# Master_MicroController_LED_Driver.net
KiCad netlist of a schematic drawn in Altium Designer
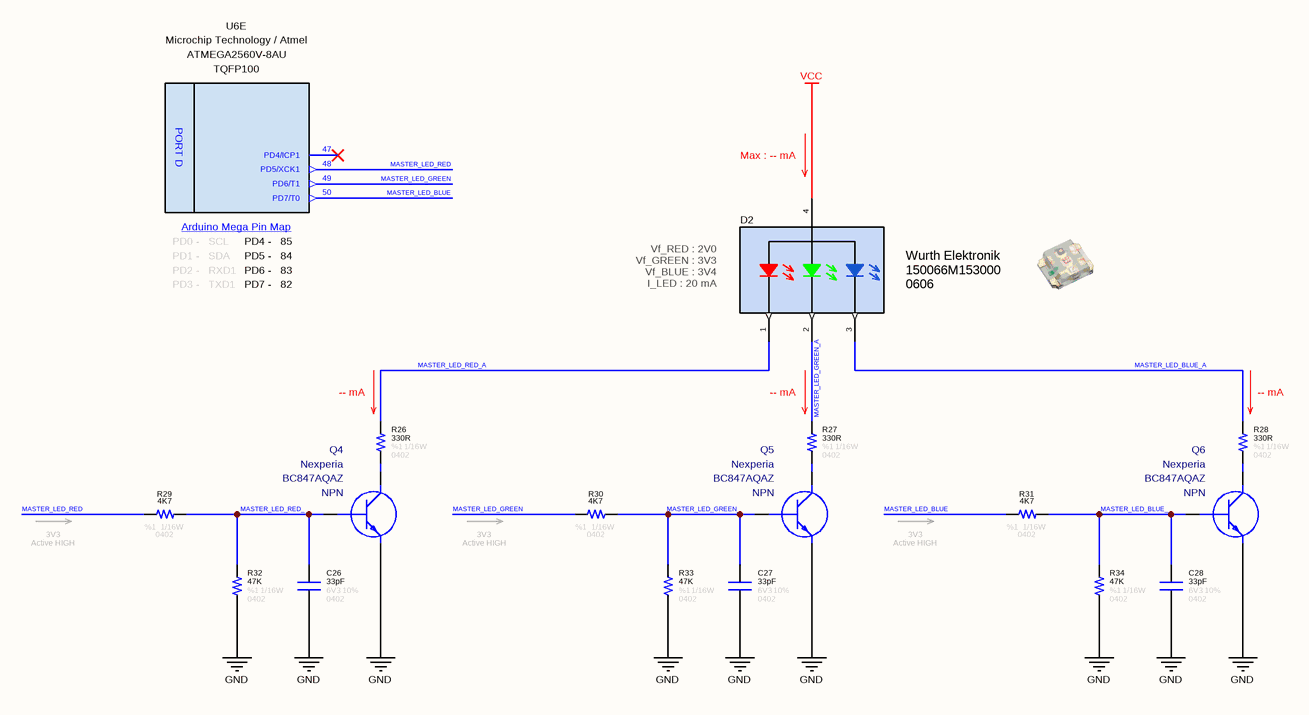
[diagram p0: Master MicroController LED Driver.SchDoc]

(export (version "E")
  (design (tool "Eeschema 10.0.6"))
  (components
    (comp (ref "C26")
      (value "33pF")
      (footprint "CAPACITOR_0402")
      (description "Capacitor - 33pF [0402] (Ceramic)")
      (fields
        (field (name "MANUFACTURER PART NUMBER") "C0402C330J9RACAUTO")
        (field (name "TOLERANCE") "10%")
        (field (name "CASE") "0402")
        (field (name "VOLTAGE") "6V3")
      )
      (libsource (lib "P101DA_Library") (part "Capacitor - 33pF [0402-6V3]"))
    )
    (comp (ref "C27")
      (value "33pF")
      (footprint "CAPACITOR_0402")
      (description "Capacitor - 33pF [0402] (Ceramic)")
      (fields
        (field (name "MANUFACTURER PART NUMBER") "C0402C330J9RACAUTO")
        (field (name "TOLERANCE") "10%")
        (field (name "CASE") "0402")
        (field (name "VOLTAGE") "6V3")
      )
      (libsource (lib "P101DA_Library") (part "Capacitor - 33pF [0402-6V3]"))
    )
    (comp (ref "C28")
      (value "33pF")
      (footprint "CAPACITOR_0402")
      (description "Capacitor - 33pF [0402] (Ceramic)")
      (fields
        (field (name "MANUFACTURER PART NUMBER") "C0402C330J9RACAUTO")
        (field (name "TOLERANCE") "10%")
        (field (name "CASE") "0402")
        (field (name "VOLTAGE") "6V3")
      )
      (libsource (lib "P101DA_Library") (part "Capacitor - 33pF [0402-6V3]"))
    )
    (comp (ref "D2")
      (value "150066M153000")
      (footprint "Wurth_0606")
      (description "LED RGB DIFFUSED SMD")
      (fields
        (field (name "MANUFACTURER NAME") "Wurth Elektronik")
        (field (name "MANUFACTURER PART NUMBER") "150066M153000")
        (field (name "CASE") "0606")
      )
      (libsource (lib "P101DA_Library") (part "Diode - LED-RGB"))
    )
    (comp (ref "Q4")
      (value "BC847AQAZ")
      (footprint "SOT1215")
      (description "Bipolar NPN Transistors")
      (fields
        (field (name "MANUFACTURER NAME") "Nexperia")
        (field (name "MANUFACTURER PART NUMBER") "BC847AQAZ")
        (field (name "POLARITY") "NPN")
      )
      (libsource (lib "P101DA_Library") (part "Transistor - BC847"))
    )
    (comp (ref "Q5")
      (value "BC847AQAZ")
      (footprint "SOT1215")
      (description "Bipolar NPN Transistors")
      (fields
        (field (name "MANUFACTURER NAME") "Nexperia")
        (field (name "MANUFACTURER PART NUMBER") "BC847AQAZ")
        (field (name "POLARITY") "NPN")
      )
      (libsource (lib "P101DA_Library") (part "Transistor - BC847"))
    )
    (comp (ref "Q6")
      (value "BC847AQAZ")
      (footprint "SOT1215")
      (description "Bipolar NPN Transistors")
      (fields
        (field (name "MANUFACTURER NAME") "Nexperia")
        (field (name "MANUFACTURER PART NUMBER") "BC847AQAZ")
        (field (name "POLARITY") "NPN")
      )
      (libsource (lib "P101DA_Library") (part "Transistor - BC847"))
    )
    (comp (ref "R26")
      (value "330R")
      (footprint "RESISTOR_0402")
      (description "Thick Film Resistors - SMD 1/16 W 330 Ohm 1%")
      (fields
        (field (name "MANUFACTURER PART NUMBER") "CRCW0402330RFKED")
        (field (name "CASE") "0402")
        (field (name "TOLERANCE") "%1")
        (field (name "POWER") "1/16W")
        (field (name "Comment") "330R - 0402 - %1 - 1/16W")
      )
      (libsource (lib "P101DA_Library") (part "Resistor - 330R [0402]"))
    )
    (comp (ref "R27")
      (value "330R")
      (footprint "RESISTOR_0402")
      (description "Thick Film Resistors - SMD 1/16 W 330 Ohm 1%")
      (fields
        (field (name "MANUFACTURER PART NUMBER") "CRCW0402330RFKED")
        (field (name "CASE") "0402")
        (field (name "TOLERANCE") "%1")
        (field (name "POWER") "1/16W")
        (field (name "Comment") "330R - 0402 - %1 - 1/16W")
      )
      (libsource (lib "P101DA_Library") (part "Resistor - 330R [0402]"))
    )
    (comp (ref "R28")
      (value "330R")
      (footprint "RESISTOR_0402")
      (description "Thick Film Resistors - SMD 1/16 W 330 Ohm 1%")
      (fields
        (field (name "MANUFACTURER PART NUMBER") "CRCW0402330RFKED")
        (field (name "CASE") "0402")
        (field (name "TOLERANCE") "%1")
        (field (name "POWER") "1/16W")
        (field (name "Comment") "330R - 0402 - %1 - 1/16W")
      )
      (libsource (lib "P101DA_Library") (part "Resistor - 330R [0402]"))
    )
    (comp (ref "R29")
      (value "4K7")
      (footprint "RESISTOR_0402")
      (description "Thick Film Resistors - SMD 1/16 W 4.7 KOhm 1%")
      (fields
        (field (name "MANUFACTURER PART NUMBER") "CRCW04024K70FKED")
        (field (name "TOLERANCE") "%1")
        (field (name "CASE") "0402")
        (field (name "POWER") "1/16W")
        (field (name "Comment") "4K7 - 0402 - %1 - 1/16W")
      )
      (libsource (lib "P101DA_Library") (part "Resistor - 4K7 [0402]"))
    )
    (comp (ref "R30")
      (value "4K7")
      (footprint "RESISTOR_0402")
      (description "Thick Film Resistors - SMD 1/16 W 4.7 KOhm 1%")
      (fields
        (field (name "MANUFACTURER PART NUMBER") "CRCW04024K70FKED")
        (field (name "TOLERANCE") "%1")
        (field (name "CASE") "0402")
        (field (name "POWER") "1/16W")
        (field (name "Comment") "4K7 - 0402 - %1 - 1/16W")
      )
      (libsource (lib "P101DA_Library") (part "Resistor - 4K7 [0402]"))
    )
    (comp (ref "R31")
      (value "4K7")
      (footprint "RESISTOR_0402")
      (description "Thick Film Resistors - SMD 1/16 W 4.7 KOhm 1%")
      (fields
        (field (name "MANUFACTURER PART NUMBER") "CRCW04024K70FKED")
        (field (name "TOLERANCE") "%1")
        (field (name "CASE") "0402")
        (field (name "POWER") "1/16W")
        (field (name "Comment") "4K7 - 0402 - %1 - 1/16W")
      )
      (libsource (lib "P101DA_Library") (part "Resistor - 4K7 [0402]"))
    )
    (comp (ref "R32")
      (value "47K")
      (footprint "RESISTOR_0402")
      (description "Thick Film Resistors - SMD 1/16 W 47 KOhm 1%")
      (fields
        (field (name "MANUFACTURER PART NUMBER") "CRCW040247K0FKED")
        (field (name "TOLERANCE") "%1")
        (field (name "CASE") "0402")
        (field (name "POWER") "1/16W")
        (field (name "Comment") "47K - 0402 - %1 - 1/16W")
      )
      (libsource (lib "P101DA_Library") (part "Resistor - 47K [0402]"))
    )
    (comp (ref "R33")
      (value "47K")
      (footprint "RESISTOR_0402")
      (description "Thick Film Resistors - SMD 1/16 W 47 KOhm 1%")
      (fields
        (field (name "MANUFACTURER PART NUMBER") "CRCW040247K0FKED")
        (field (name "TOLERANCE") "%1")
        (field (name "CASE") "0402")
        (field (name "POWER") "1/16W")
        (field (name "Comment") "47K - 0402 - %1 - 1/16W")
      )
      (libsource (lib "P101DA_Library") (part "Resistor - 47K [0402]"))
    )
    (comp (ref "R34")
      (value "47K")
      (footprint "RESISTOR_0402")
      (description "Thick Film Resistors - SMD 1/16 W 47 KOhm 1%")
      (fields
        (field (name "MANUFACTURER PART NUMBER") "CRCW040247K0FKED")
        (field (name "TOLERANCE") "%1")
        (field (name "CASE") "0402")
        (field (name "POWER") "1/16W")
        (field (name "Comment") "47K - 0402 - %1 - 1/16W")
      )
      (libsource (lib "P101DA_Library") (part "Resistor - 47K [0402]"))
    )
    (comp (ref "U6")
      (value "ATMEGA2560V-8AU")
      (footprint "TQFP-100")
      (description "ATmega Series 256 KB Flash 8 KB SRAM 8 MHz 8-Bit Microcontroller - TQFP-100")
      (fields
        (field (name "MANUFACTURER NAME") "Microchip Technology / Atmel")
        (field (name "MANUFACTURER PART NUMBER") "ATMEGA2560V-8AU")
        (field (name "CASE") "TQFP100")
      )
      (libsource (lib "P101DA_Library") (part "IC - AtMega2560V-8AU"))
    )
  )
  (nets
    (net (code "1") (name "/MASTER_LED_BLUE") (class "Default")
      (node (ref "R31") (pin "2") (pinfunction "2_2") (pintype "passive"))
      (node (ref "U6") (pin "50") (pinfunction "PD7/T0_50") (pintype "output"))
    )
    (net (code "2") (name "/MASTER_LED_BLUE_") (class "Default")
      (node (ref "C28") (pin "2") (pinfunction "2_2") (pintype "passive"))
      (node (ref "Q6") (pin "1") (pinfunction "B_1") (pintype "passive"))
      (node (ref "R31") (pin "1") (pinfunction "1_1") (pintype "passive"))
      (node (ref "R34") (pin "2") (pinfunction "2_2") (pintype "passive"))
    )
    (net (code "3") (name "/MASTER_LED_BLUE_A") (class "Default")
      (node (ref "D2") (pin "3") (pinfunction "3_3") (pintype "output"))
      (node (ref "R28") (pin "2") (pinfunction "2_2") (pintype "passive"))
    )
    (net (code "4") (name "/MASTER_LED_GREEN") (class "Default")
      (node (ref "R30") (pin "2") (pinfunction "2_2") (pintype "passive"))
      (node (ref "U6") (pin "49") (pinfunction "PD6/T1_49") (pintype "output"))
    )
    (net (code "5") (name "/MASTER_LED_GREEN_") (class "Default")
      (node (ref "C27") (pin "2") (pinfunction "2_2") (pintype "passive"))
      (node (ref "Q5") (pin "1") (pinfunction "B_1") (pintype "passive"))
      (node (ref "R30") (pin "1") (pinfunction "1_1") (pintype "passive"))
      (node (ref "R33") (pin "2") (pinfunction "2_2") (pintype "passive"))
    )
    (net (code "6") (name "/MASTER_LED_GREEN_A") (class "Default")
      (node (ref "D2") (pin "2") (pinfunction "2_2") (pintype "output"))
      (node (ref "R27") (pin "2") (pinfunction "2_2") (pintype "passive"))
    )
    (net (code "7") (name "/MASTER_LED_RED") (class "Default")
      (node (ref "R29") (pin "2") (pinfunction "2_2") (pintype "passive"))
      (node (ref "U6") (pin "48") (pinfunction "PD5/XCK1_48") (pintype "output"))
    )
    (net (code "8") (name "/MASTER_LED_RED_") (class "Default")
      (node (ref "C26") (pin "2") (pinfunction "2_2") (pintype "passive"))
      (node (ref "Q4") (pin "1") (pinfunction "B_1") (pintype "passive"))
      (node (ref "R29") (pin "1") (pinfunction "1_1") (pintype "passive"))
      (node (ref "R32") (pin "2") (pinfunction "2_2") (pintype "passive"))
    )
    (net (code "9") (name "/MASTER_LED_RED_A") (class "Default")
      (node (ref "D2") (pin "1") (pinfunction "1_1") (pintype "output"))
      (node (ref "R26") (pin "2") (pinfunction "2_2") (pintype "passive"))
    )
    (net (code "10") (name "GND") (class "Default")
      (node (ref "C26") (pin "1") (pinfunction "1_1") (pintype "passive"))
      (node (ref "C27") (pin "1") (pinfunction "1_1") (pintype "passive"))
      (node (ref "C28") (pin "1") (pinfunction "1_1") (pintype "passive"))
      (node (ref "Q4") (pin "2") (pinfunction "E_2") (pintype "passive"))
      (node (ref "Q5") (pin "2") (pinfunction "E_2") (pintype "passive"))
      (node (ref "Q6") (pin "2") (pinfunction "E_2") (pintype "passive"))
      (node (ref "R32") (pin "1") (pinfunction "1_1") (pintype "passive"))
      (node (ref "R33") (pin "1") (pinfunction "1_1") (pintype "passive"))
      (node (ref "R34") (pin "1") (pinfunction "1_1") (pintype "passive"))
    )
    (net (code "11") (name "Net-(Q4-C)") (class "Default")
      (node (ref "Q4") (pin "3") (pinfunction "C_3") (pintype "passive"))
      (node (ref "R26") (pin "1") (pinfunction "1_1") (pintype "passive"))
    )
    (net (code "12") (name "Net-(Q5-C)") (class "Default")
      (node (ref "Q5") (pin "3") (pinfunction "C_3") (pintype "passive"))
      (node (ref "R27") (pin "1") (pinfunction "1_1") (pintype "passive"))
    )
    (net (code "13") (name "Net-(Q6-C)") (class "Default")
      (node (ref "Q6") (pin "3") (pinfunction "C_3") (pintype "passive"))
      (node (ref "R28") (pin "1") (pinfunction "1_1") (pintype "passive"))
    )
    (net (code "14") (name "VCC") (class "Default")
      (node (ref "D2") (pin "4") (pinfunction "4_4") (pintype "power_in"))
    )
    (net (code "15") (name "unconnected-(U6E-PD4{slash}ICP1-Pad47)") (class "Default")
      (node (ref "U6") (pin "47") (pinfunction "PD4/ICP1_47") (pintype "passive+no_connect"))
    )
  )
)
